# CadenceSense2_0.net
KiCad netlist of a schematic drawn in EAGLE
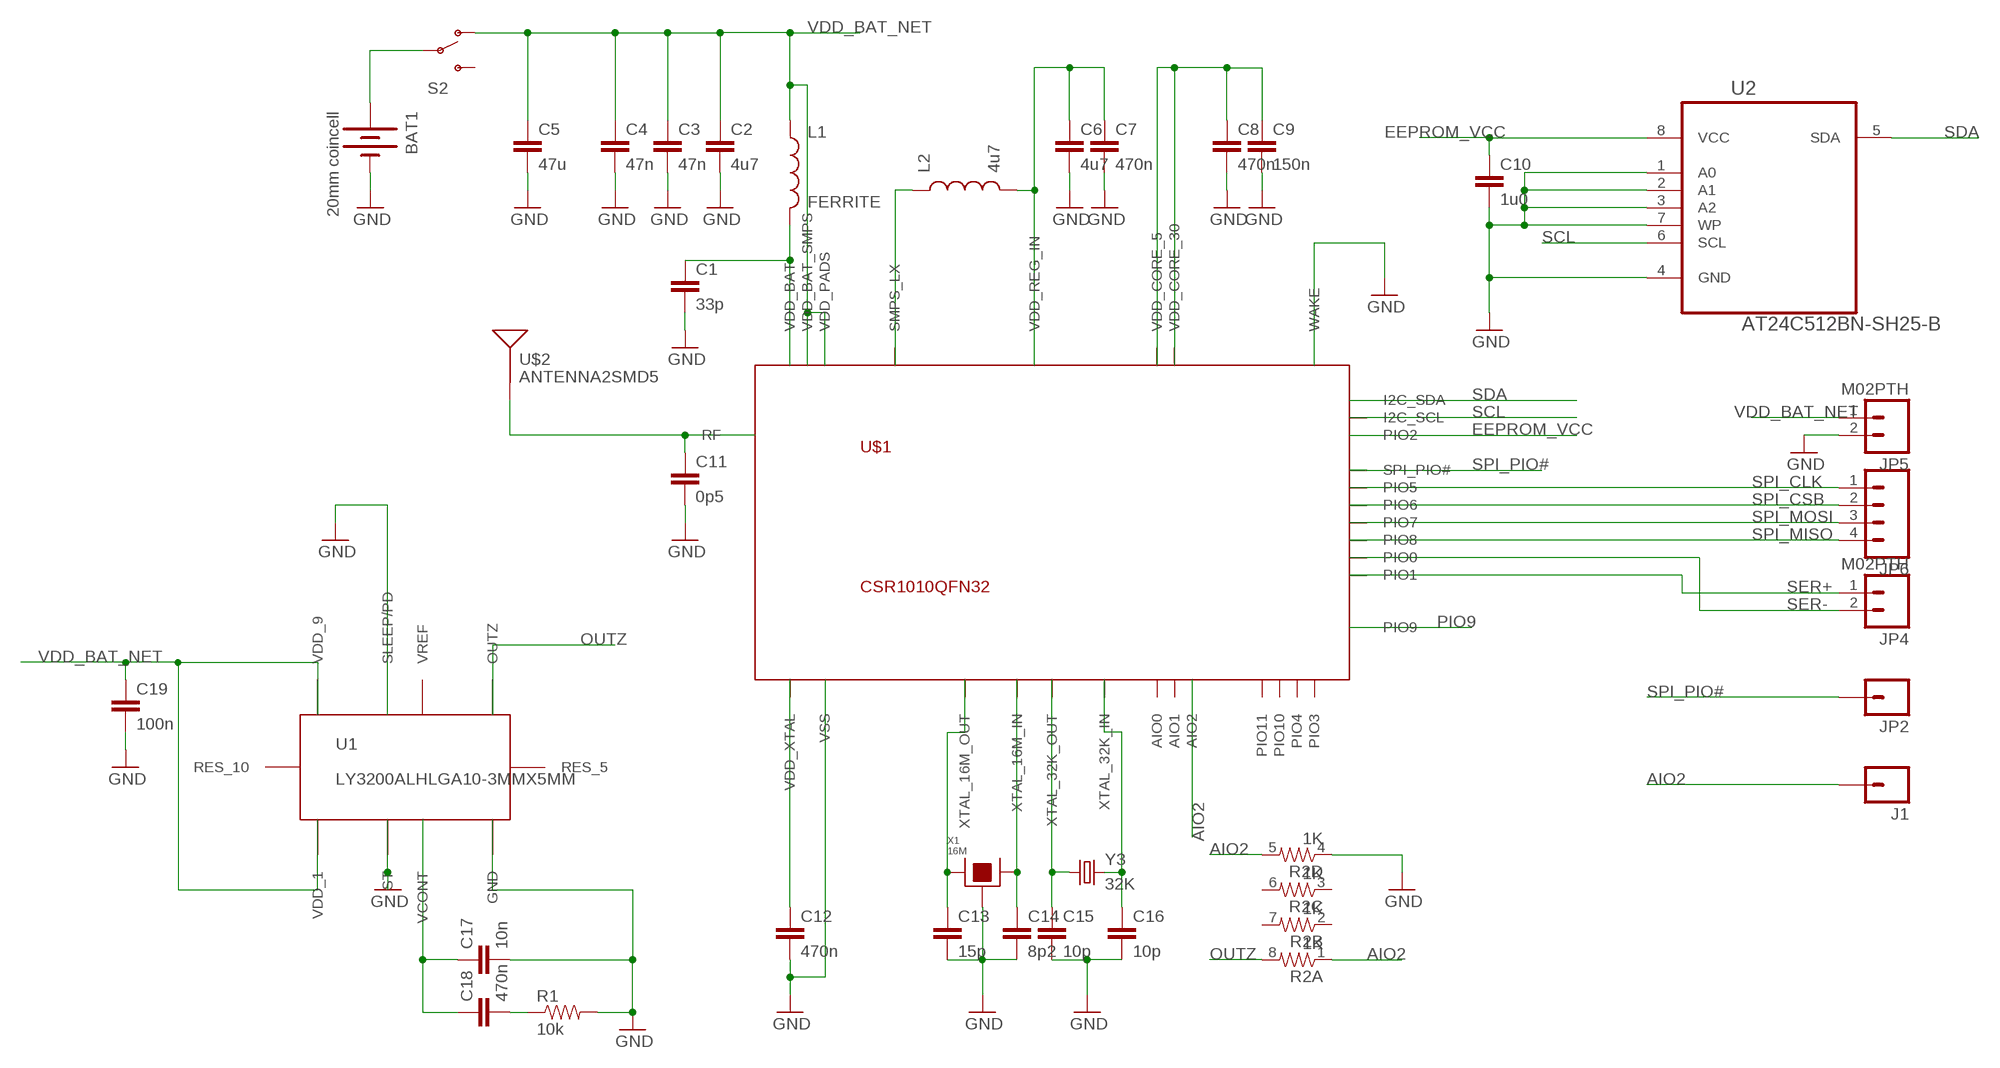
[diagram p0: schematic, sheet 1]

(export (version "E")
  (design (tool "Eeschema 10.0.6"))
  (components
    (comp (ref "BAT1")
      (value "20mm coincell")
      (footprint "eagle-import:BATTCON_20MM_4LEGS")
      (libsource (lib "eagle-import") (part "BATTERY20MM_4LEGS"))
    )
    (comp (ref "C1")
      (value "33p")
      (footprint "eagle-import:0603-CAP")
      (libsource (lib "eagle-import") (part "CAP0603-CAP"))
    )
    (comp (ref "C2")
      (value "4u7")
      (footprint "eagle-import:0603-CAP")
      (libsource (lib "eagle-import") (part "CAP0603-CAP"))
    )
    (comp (ref "C3")
      (value "47n")
      (footprint "eagle-import:0603-CAP")
      (libsource (lib "eagle-import") (part "CAP0603-CAP"))
    )
    (comp (ref "C4")
      (value "47n")
      (footprint "eagle-import:0603-CAP")
      (libsource (lib "eagle-import") (part "CAP0603-CAP"))
    )
    (comp (ref "C5")
      (value "47u")
      (footprint "eagle-import:0603-CAP")
      (libsource (lib "eagle-import") (part "CAP0603-CAP"))
    )
    (comp (ref "C6")
      (value "4u7")
      (footprint "eagle-import:0603-CAP")
      (libsource (lib "eagle-import") (part "CAP0603-CAP"))
    )
    (comp (ref "C7")
      (value "470n")
      (footprint "eagle-import:0603-CAP")
      (libsource (lib "eagle-import") (part "CAP0603-CAP"))
    )
    (comp (ref "C8")
      (value "470n")
      (footprint "eagle-import:0603-CAP")
      (libsource (lib "eagle-import") (part "CAP0603-CAP"))
    )
    (comp (ref "C9")
      (value "150n")
      (footprint "eagle-import:0603-CAP")
      (libsource (lib "eagle-import") (part "CAP0603-CAP"))
    )
    (comp (ref "C10")
      (value "1u0")
      (footprint "eagle-import:0603-CAP")
      (libsource (lib "eagle-import") (part "CAP0603-CAP"))
    )
    (comp (ref "C11")
      (value "0p5")
      (footprint "eagle-import:0603-CAP")
      (libsource (lib "eagle-import") (part "CAP0603-CAP"))
    )
    (comp (ref "C12")
      (value "470n")
      (footprint "eagle-import:0603-CAP")
      (libsource (lib "eagle-import") (part "CAP0603-CAP"))
    )
    (comp (ref "C13")
      (value "15p")
      (footprint "eagle-import:0603-CAP")
      (libsource (lib "eagle-import") (part "CAP0603-CAP"))
    )
    (comp (ref "C14")
      (value "8p2")
      (footprint "eagle-import:0603-CAP")
      (libsource (lib "eagle-import") (part "CAP0603-CAP"))
    )
    (comp (ref "C15")
      (value "10p")
      (footprint "eagle-import:0603-CAP")
      (libsource (lib "eagle-import") (part "CAP0603-CAP"))
    )
    (comp (ref "C16")
      (value "10p")
      (footprint "eagle-import:0603-CAP")
      (libsource (lib "eagle-import") (part "CAP0603-CAP"))
    )
    (comp (ref "C17")
      (value "10n")
      (footprint "eagle-import:0603-CAP")
      (libsource (lib "eagle-import") (part "CAP0603-CAP"))
    )
    (comp (ref "C18")
      (value "470n")
      (footprint "eagle-import:0603-CAP")
      (libsource (lib "eagle-import") (part "CAP0603-CAP"))
    )
    (comp (ref "C19")
      (value "100n")
      (footprint "eagle-import:0603-CAP")
      (libsource (lib "eagle-import") (part "CAP0603-CAP"))
    )
    (comp (ref "J1")
      (value "M01PTH")
      (footprint "eagle-import:1X01")
      (libsource (lib "eagle-import") (part "M01PTH"))
    )
    (comp (ref "JP2")
      (value "M01PTH")
      (footprint "eagle-import:1X01")
      (libsource (lib "eagle-import") (part "M01PTH"))
    )
    (comp (ref "JP4")
      (value "M02PTH")
      (footprint "eagle-import:1X02")
      (libsource (lib "eagle-import") (part "M02PTH"))
    )
    (comp (ref "JP5")
      (value "M02PTH")
      (footprint "eagle-import:1X02")
      (libsource (lib "eagle-import") (part "M02PTH"))
    )
    (comp (ref "JP6")
      (value "M04PTH")
      (footprint "eagle-import:1X04")
      (libsource (lib "eagle-import") (part "M04PTH"))
    )
    (comp (ref "L1")
      (value "FERRITE")
      (footprint "eagle-import:0805")
      (libsource (lib "eagle-import") (part "INDUCTOR0805"))
    )
    (comp (ref "L2")
      (value "4u7")
      (footprint "eagle-import:0805")
      (libsource (lib "eagle-import") (part "INDUCTOR0805"))
    )
    (comp (ref "R1")
      (value "10k")
      (footprint "eagle-import:0603-RES")
      (libsource (lib "eagle-import") (part "RESISTOR0603-RES"))
    )
    (comp (ref "R2")
      (value "1K")
      (footprint "eagle-import:0603-ARV")
      (libsource (lib "eagle-import") (part "RESISTOR-ARRAY0603-ARV"))
    )
    (comp (ref "S2")
      (value "SWITCH-SPDTSMD")
      (footprint "eagle-import:AYZ0202")
      (libsource (lib "eagle-import") (part "SWITCH-SPDTSMD"))
    )
    (comp (ref "U$1")
      (value "CSR1010QFN32")
      (footprint "eagle-import:QFN-32")
      (libsource (lib "eagle-import") (part "CSR1010QFN32"))
    )
    (comp (ref "U$2")
      (value "ANTENNA2SMD5")
      (footprint "eagle-import:ANTENNA-CHIP5")
      (libsource (lib "eagle-import") (part "ANTENNA2SMD5"))
    )
    (comp (ref "U1")
      (value "LY3200ALHLGA10-3MMX5MM")
      (footprint "eagle-import:LGA10")
      (libsource (lib "eagle-import") (part "LY3200ALHLGA10-3MMX5MM"))
    )
    (comp (ref "U2")
      (value "AT24C512BN-SH25-B")
      (footprint "eagle-import:SOIC127P600X175-8N")
      (libsource (lib "eagle-import") (part "AT24C512BN-SH25-B"))
    )
    (comp (ref "X1")
      (value "16M")
      (footprint "eagle-import:TSX-3225")
      (libsource (lib "eagle-import") (part "SHIELDED_CRYSTAL_TSX-3225"))
    )
    (comp (ref "Y3")
      (value "32K")
      (footprint "eagle-import:CRYSTAL-32KHZ-SMD_EPSON_MC146")
      (libsource (lib "eagle-import") (part "CRYSTALEPSONMC146"))
    )
  )
  (nets
    (net (code "1") (name "/AIO2") (class "Default")
      (node (ref "J1") (pin "1") (pinfunction "1_1") (pintype "passive"))
      (node (ref "R2") (pin "1") (pinfunction "1_1") (pintype "passive"))
      (node (ref "R2") (pin "5") (pinfunction "2_5") (pintype "passive"))
      (node (ref "U$1") (pin "11") (pinfunction "AIO2_11") (pintype "bidirectional"))
    )
    (net (code "2") (name "/EEPROM_VCC") (class "Default")
      (node (ref "C10") (pin "1") (pinfunction "1_1") (pintype "passive"))
      (node (ref "U$1") (pin "27") (pinfunction "PIO2_27") (pintype "bidirectional"))
      (node (ref "U2") (pin "8") (pinfunction "VCC_8") (pintype "power_in"))
    )
    (net (code "3") (name "/OUTZ") (class "Default")
      (node (ref "R2") (pin "8") (pinfunction "2_8") (pintype "passive"))
      (node (ref "U1") (pin "6") (pinfunction "OUTZ_6") (pintype "bidirectional"))
    )
    (net (code "4") (name "/PIO9") (class "Default")
      (node (ref "U$1") (pin "23") (pinfunction "PIO9_23") (pintype "bidirectional"))
    )
    (net (code "5") (name "/SCL") (class "Default")
      (node (ref "U$1") (pin "28") (pinfunction "I2C_SCL_28") (pintype "bidirectional"))
      (node (ref "U2") (pin "6") (pinfunction "SCL_6") (pintype "input"))
    )
    (net (code "6") (name "/SDA") (class "Default")
      (node (ref "U$1") (pin "29") (pinfunction "I2C_SDA_29") (pintype "bidirectional"))
      (node (ref "U2") (pin "5") (pinfunction "SDA_5") (pintype "bidirectional"))
    )
    (net (code "7") (name "/SER+") (class "Default")
      (node (ref "JP4") (pin "1") (pinfunction "1_1") (pintype "passive"))
      (node (ref "U$1") (pin "15") (pinfunction "PIO1_15") (pintype "bidirectional"))
    )
    (net (code "8") (name "/SER-") (class "Default")
      (node (ref "JP4") (pin "2") (pinfunction "2_2") (pintype "passive"))
      (node (ref "U$1") (pin "14") (pinfunction "PIO0_14") (pintype "bidirectional"))
    )
    (net (code "9") (name "/SPI_CLK") (class "Default")
      (node (ref "JP6") (pin "1") (pinfunction "1_1") (pintype "passive"))
      (node (ref "U$1") (pin "18") (pinfunction "PIO5_18") (pintype "bidirectional"))
    )
    (net (code "10") (name "/SPI_CSB") (class "Default")
      (node (ref "JP6") (pin "2") (pinfunction "2_2") (pintype "passive"))
      (node (ref "U$1") (pin "19") (pinfunction "PIO6_19") (pintype "bidirectional"))
    )
    (net (code "11") (name "/SPI_MISO") (class "Default")
      (node (ref "JP6") (pin "4") (pinfunction "4_4") (pintype "passive"))
      (node (ref "U$1") (pin "22") (pinfunction "PIO8_22") (pintype "bidirectional"))
    )
    (net (code "12") (name "/SPI_MOSI") (class "Default")
      (node (ref "JP6") (pin "3") (pinfunction "3_3") (pintype "passive"))
      (node (ref "U$1") (pin "20") (pinfunction "PIO7_20") (pintype "bidirectional"))
    )
    (net (code "13") (name "/SPI_PIO#") (class "Default")
      (node (ref "JP2") (pin "1") (pinfunction "1_1") (pintype "passive"))
      (node (ref "U$1") (pin "26") (pinfunction "SPI_PIO#_26") (pintype "bidirectional"))
    )
    (net (code "14") (name "/VDD_BAT_NET") (class "Default")
      (node (ref "C19") (pin "1") (pinfunction "1_1") (pintype "passive"))
      (node (ref "C2") (pin "1") (pinfunction "1_1") (pintype "passive"))
      (node (ref "C3") (pin "1") (pinfunction "1_1") (pintype "passive"))
      (node (ref "C4") (pin "1") (pinfunction "1_1") (pintype "passive"))
      (node (ref "C5") (pin "1") (pinfunction "1_1") (pintype "passive"))
      (node (ref "JP5") (pin "1") (pinfunction "1_1") (pintype "passive"))
      (node (ref "L1") (pin "1") (pinfunction "1_1") (pintype "passive"))
      (node (ref "S2") (pin "1") (pinfunction "O_1") (pintype "passive"))
      (node (ref "U$1") (pin "21") (pinfunction "VDD_PADS_21") (pintype "power_in"))
      (node (ref "U$1") (pin "32") (pinfunction "VDD_BAT_SMPS_32") (pintype "power_in"))
      (node (ref "U1") (pin "1") (pinfunction "VDD_1_1") (pintype "power_in"))
      (node (ref "U1") (pin "9") (pinfunction "VDD_9_9") (pintype "power_in"))
    )
    (net (code "15") (name "GND") (class "Default")
      (node (ref "BAT1") (pin "2") (pinfunction "-_2") (pintype "power_in"))
      (node (ref "C1") (pin "2") (pinfunction "2_2") (pintype "passive"))
      (node (ref "C10") (pin "2") (pinfunction "2_2") (pintype "passive"))
      (node (ref "C11") (pin "2") (pinfunction "2_2") (pintype "passive"))
      (node (ref "C12") (pin "2") (pinfunction "2_2") (pintype "passive"))
      (node (ref "C13") (pin "2") (pinfunction "2_2") (pintype "passive"))
      (node (ref "C14") (pin "2") (pinfunction "2_2") (pintype "passive"))
      (node (ref "C15") (pin "2") (pinfunction "2_2") (pintype "passive"))
      (node (ref "C16") (pin "2") (pinfunction "2_2") (pintype "passive"))
      (node (ref "C17") (pin "2") (pinfunction "2_2") (pintype "passive"))
      (node (ref "C19") (pin "2") (pinfunction "2_2") (pintype "passive"))
      (node (ref "C2") (pin "2") (pinfunction "2_2") (pintype "passive"))
      (node (ref "C3") (pin "2") (pinfunction "2_2") (pintype "passive"))
      (node (ref "C4") (pin "2") (pinfunction "2_2") (pintype "passive"))
      (node (ref "C5") (pin "2") (pinfunction "2_2") (pintype "passive"))
      (node (ref "C6") (pin "2") (pinfunction "2_2") (pintype "passive"))
      (node (ref "C7") (pin "2") (pinfunction "2_2") (pintype "passive"))
      (node (ref "C8") (pin "2") (pinfunction "2_2") (pintype "passive"))
      (node (ref "C9") (pin "2") (pinfunction "2_2") (pintype "passive"))
      (node (ref "JP5") (pin "2") (pinfunction "2_2") (pintype "passive"))
      (node (ref "R1") (pin "2") (pinfunction "2_2") (pintype "passive"))
      (node (ref "R2") (pin "4") (pinfunction "1_4") (pintype "passive"))
      (node (ref "U$1") (pin "4") (pinfunction "WAKE_4") (pintype "bidirectional"))
      (node (ref "U$1") (pin "EP") (pinfunction "VSS_EP") (pintype "power_in"))
      (node (ref "U1") (pin "2") (pinfunction "ST_2") (pintype "input"))
      (node (ref "U1") (pin "4") (pinfunction "GND_4") (pintype "power_in"))
      (node (ref "U1") (pin "8") (pinfunction "SLEEP/PD_8") (pintype "input"))
      (node (ref "U2") (pin "1") (pinfunction "A0_1") (pintype "input"))
      (node (ref "U2") (pin "2") (pinfunction "A1_2") (pintype "input"))
      (node (ref "U2") (pin "3") (pinfunction "A2_3") (pintype "input"))
      (node (ref "U2") (pin "4") (pinfunction "GND_4") (pintype "passive"))
      (node (ref "U2") (pin "7") (pinfunction "WP_7") (pintype "input"))
      (node (ref "X1") (pin "2") (pinfunction "P$3_2") (pintype "bidirectional"))
      (node (ref "X1") (pin "4") (pinfunction "P$3_4") (pintype "bidirectional"))
    )
    (net (code "16") (name "Net-(BAT1-+)") (class "Default")
      (node (ref "BAT1") (pin "1") (pinfunction "+_1") (pintype "power_in"))
      (node (ref "S2") (pin "2") (pinfunction "P_2") (pintype "passive"))
    )
    (net (code "17") (name "Net-(C18-Pad2)") (class "Default")
      (node (ref "C18") (pin "2") (pinfunction "2_2") (pintype "passive"))
      (node (ref "R1") (pin "1") (pinfunction "1_1") (pintype "passive"))
    )
    (net (code "18") (name "Net-(U$1-RF)") (class "Default")
      (node (ref "C11") (pin "1") (pinfunction "1_1") (pintype "passive"))
      (node (ref "U$1") (pin "7") (pinfunction "RF_7") (pintype "bidirectional"))
      (node (ref "U$2") (pin "FEED") (pinfunction "SIGNAL_FEED") (pintype "bidirectional"))
    )
    (net (code "19") (name "Net-(U$1-SMPS_LX)") (class "Default")
      (node (ref "L2") (pin "1") (pinfunction "1_1") (pintype "passive"))
      (node (ref "U$1") (pin "31") (pinfunction "SMPS_LX_31") (pintype "power_in"))
    )
    (net (code "20") (name "Net-(U$1-VDD_BAT)") (class "Default")
      (node (ref "C1") (pin "1") (pinfunction "1_1") (pintype "passive"))
      (node (ref "L1") (pin "2") (pinfunction "2_2") (pintype "passive"))
      (node (ref "U$1") (pin "1") (pinfunction "VDD_BAT_1") (pintype "power_in"))
    )
    (net (code "21") (name "Net-(U$1-VDD_CORE_30)") (class "Default")
      (node (ref "C8") (pin "1") (pinfunction "1_1") (pintype "passive"))
      (node (ref "C9") (pin "1") (pinfunction "1_1") (pintype "passive"))
      (node (ref "U$1") (pin "30") (pinfunction "VDD_CORE_30_30") (pintype "power_in"))
      (node (ref "U$1") (pin "5") (pinfunction "VDD_CORE_5_5") (pintype "power_in"))
    )
    (net (code "22") (name "Net-(U$1-VDD_REG_IN)") (class "Default")
      (node (ref "C6") (pin "1") (pinfunction "1_1") (pintype "passive"))
      (node (ref "C7") (pin "1") (pinfunction "1_1") (pintype "passive"))
      (node (ref "L2") (pin "2") (pinfunction "2_2") (pintype "passive"))
      (node (ref "U$1") (pin "6") (pinfunction "VDD_REG_IN_6") (pintype "power_in"))
    )
    (net (code "23") (name "Net-(U$1-VDD_XTAL)") (class "Default")
      (node (ref "C12") (pin "1") (pinfunction "1_1") (pintype "passive"))
      (node (ref "U$1") (pin "8") (pinfunction "VDD_XTAL_8") (pintype "bidirectional"))
    )
    (net (code "24") (name "Net-(U$1-XTAL_16M_IN)") (class "Default")
      (node (ref "C14") (pin "1") (pinfunction "1_1") (pintype "passive"))
      (node (ref "U$1") (pin "10") (pinfunction "XTAL_16M_IN_10") (pintype "bidirectional"))
      (node (ref "X1") (pin "3") (pinfunction "P$2_3") (pintype "bidirectional"))
    )
    (net (code "25") (name "Net-(U$1-XTAL_16M_OUT)") (class "Default")
      (node (ref "C13") (pin "1") (pinfunction "1_1") (pintype "passive"))
      (node (ref "U$1") (pin "9") (pinfunction "XTAL_16M_OUT_9") (pintype "bidirectional"))
      (node (ref "X1") (pin "1") (pinfunction "P$1_1") (pintype "bidirectional"))
    )
    (net (code "26") (name "Net-(U$1-XTAL_32K_IN)") (class "Default")
      (node (ref "C16") (pin "1") (pinfunction "1_1") (pintype "passive"))
      (node (ref "U$1") (pin "3") (pinfunction "XTAL_32K_IN_3") (pintype "bidirectional"))
      (node (ref "Y3") (pin "P$1") (pinfunction "2_P$1") (pintype "passive"))
    )
    (net (code "27") (name "Net-(U$1-XTAL_32K_OUT)") (class "Default")
      (node (ref "C15") (pin "1") (pinfunction "1_1") (pintype "passive"))
      (node (ref "U$1") (pin "2") (pinfunction "XTAL_32K_OUT_2") (pintype "bidirectional"))
      (node (ref "Y3") (pin "P$2") (pinfunction "1_P$2") (pintype "passive"))
    )
    (net (code "28") (name "Net-(U1-VCONT)") (class "Default")
      (node (ref "C17") (pin "1") (pinfunction "1_1") (pintype "passive"))
      (node (ref "C18") (pin "1") (pinfunction "1_1") (pintype "passive"))
      (node (ref "U1") (pin "3") (pinfunction "VCONT_3") (pintype "bidirectional"))
    )
    (net (code "29") (name "unconnected-(R2B-1-Pad2)") (class "Default")
      (node (ref "R2") (pin "2") (pinfunction "1_2") (pintype "passive"))
    )
    (net (code "30") (name "unconnected-(R2B-2-Pad7)") (class "Default")
      (node (ref "R2") (pin "7") (pinfunction "2_7") (pintype "passive"))
    )
    (net (code "31") (name "unconnected-(R2C-1-Pad3)") (class "Default")
      (node (ref "R2") (pin "3") (pinfunction "1_3") (pintype "passive"))
    )
    (net (code "32") (name "unconnected-(R2C-2-Pad6)") (class "Default")
      (node (ref "R2") (pin "6") (pinfunction "2_6") (pintype "passive"))
    )
    (net (code "33") (name "unconnected-(S2-S-Pad3)") (class "Default")
      (node (ref "S2") (pin "3") (pinfunction "S_3") (pintype "passive"))
    )
    (net (code "34") (name "unconnected-(U$1-AIO0-Pad13)") (class "Default")
      (node (ref "U$1") (pin "13") (pinfunction "AIO0_13") (pintype "bidirectional"))
    )
    (net (code "35") (name "unconnected-(U$1-AIO1-Pad12)") (class "Default")
      (node (ref "U$1") (pin "12") (pinfunction "AIO1_12") (pintype "bidirectional"))
    )
    (net (code "36") (name "unconnected-(U$1-PIO3-Pad16)") (class "Default")
      (node (ref "U$1") (pin "16") (pinfunction "PIO3_16") (pintype "bidirectional"))
    )
    (net (code "37") (name "unconnected-(U$1-PIO4-Pad17)") (class "Default")
      (node (ref "U$1") (pin "17") (pinfunction "PIO4_17") (pintype "bidirectional"))
    )
    (net (code "38") (name "unconnected-(U$1-PIO10-Pad24)") (class "Default")
      (node (ref "U$1") (pin "24") (pinfunction "PIO10_24") (pintype "bidirectional"))
    )
    (net (code "39") (name "unconnected-(U$1-PIO11-Pad25)") (class "Default")
      (node (ref "U$1") (pin "25") (pinfunction "PIO11_25") (pintype "bidirectional"))
    )
    (net (code "40") (name "unconnected-(U1-RES_5-Pad5)") (class "Default")
      (node (ref "U1") (pin "5") (pinfunction "RES_5_5") (pintype "no_connect"))
    )
    (net (code "41") (name "unconnected-(U1-RES_10-Pad10)") (class "Default")
      (node (ref "U1") (pin "10") (pinfunction "RES_10_10") (pintype "no_connect"))
    )
    (net (code "42") (name "unconnected-(U1-VREF-Pad7)") (class "Default")
      (node (ref "U1") (pin "7") (pinfunction "VREF_7") (pintype "output"))
    )
  )
)
